# top_power.net
KiCad netlist of a schematic drawn in Altium Designer
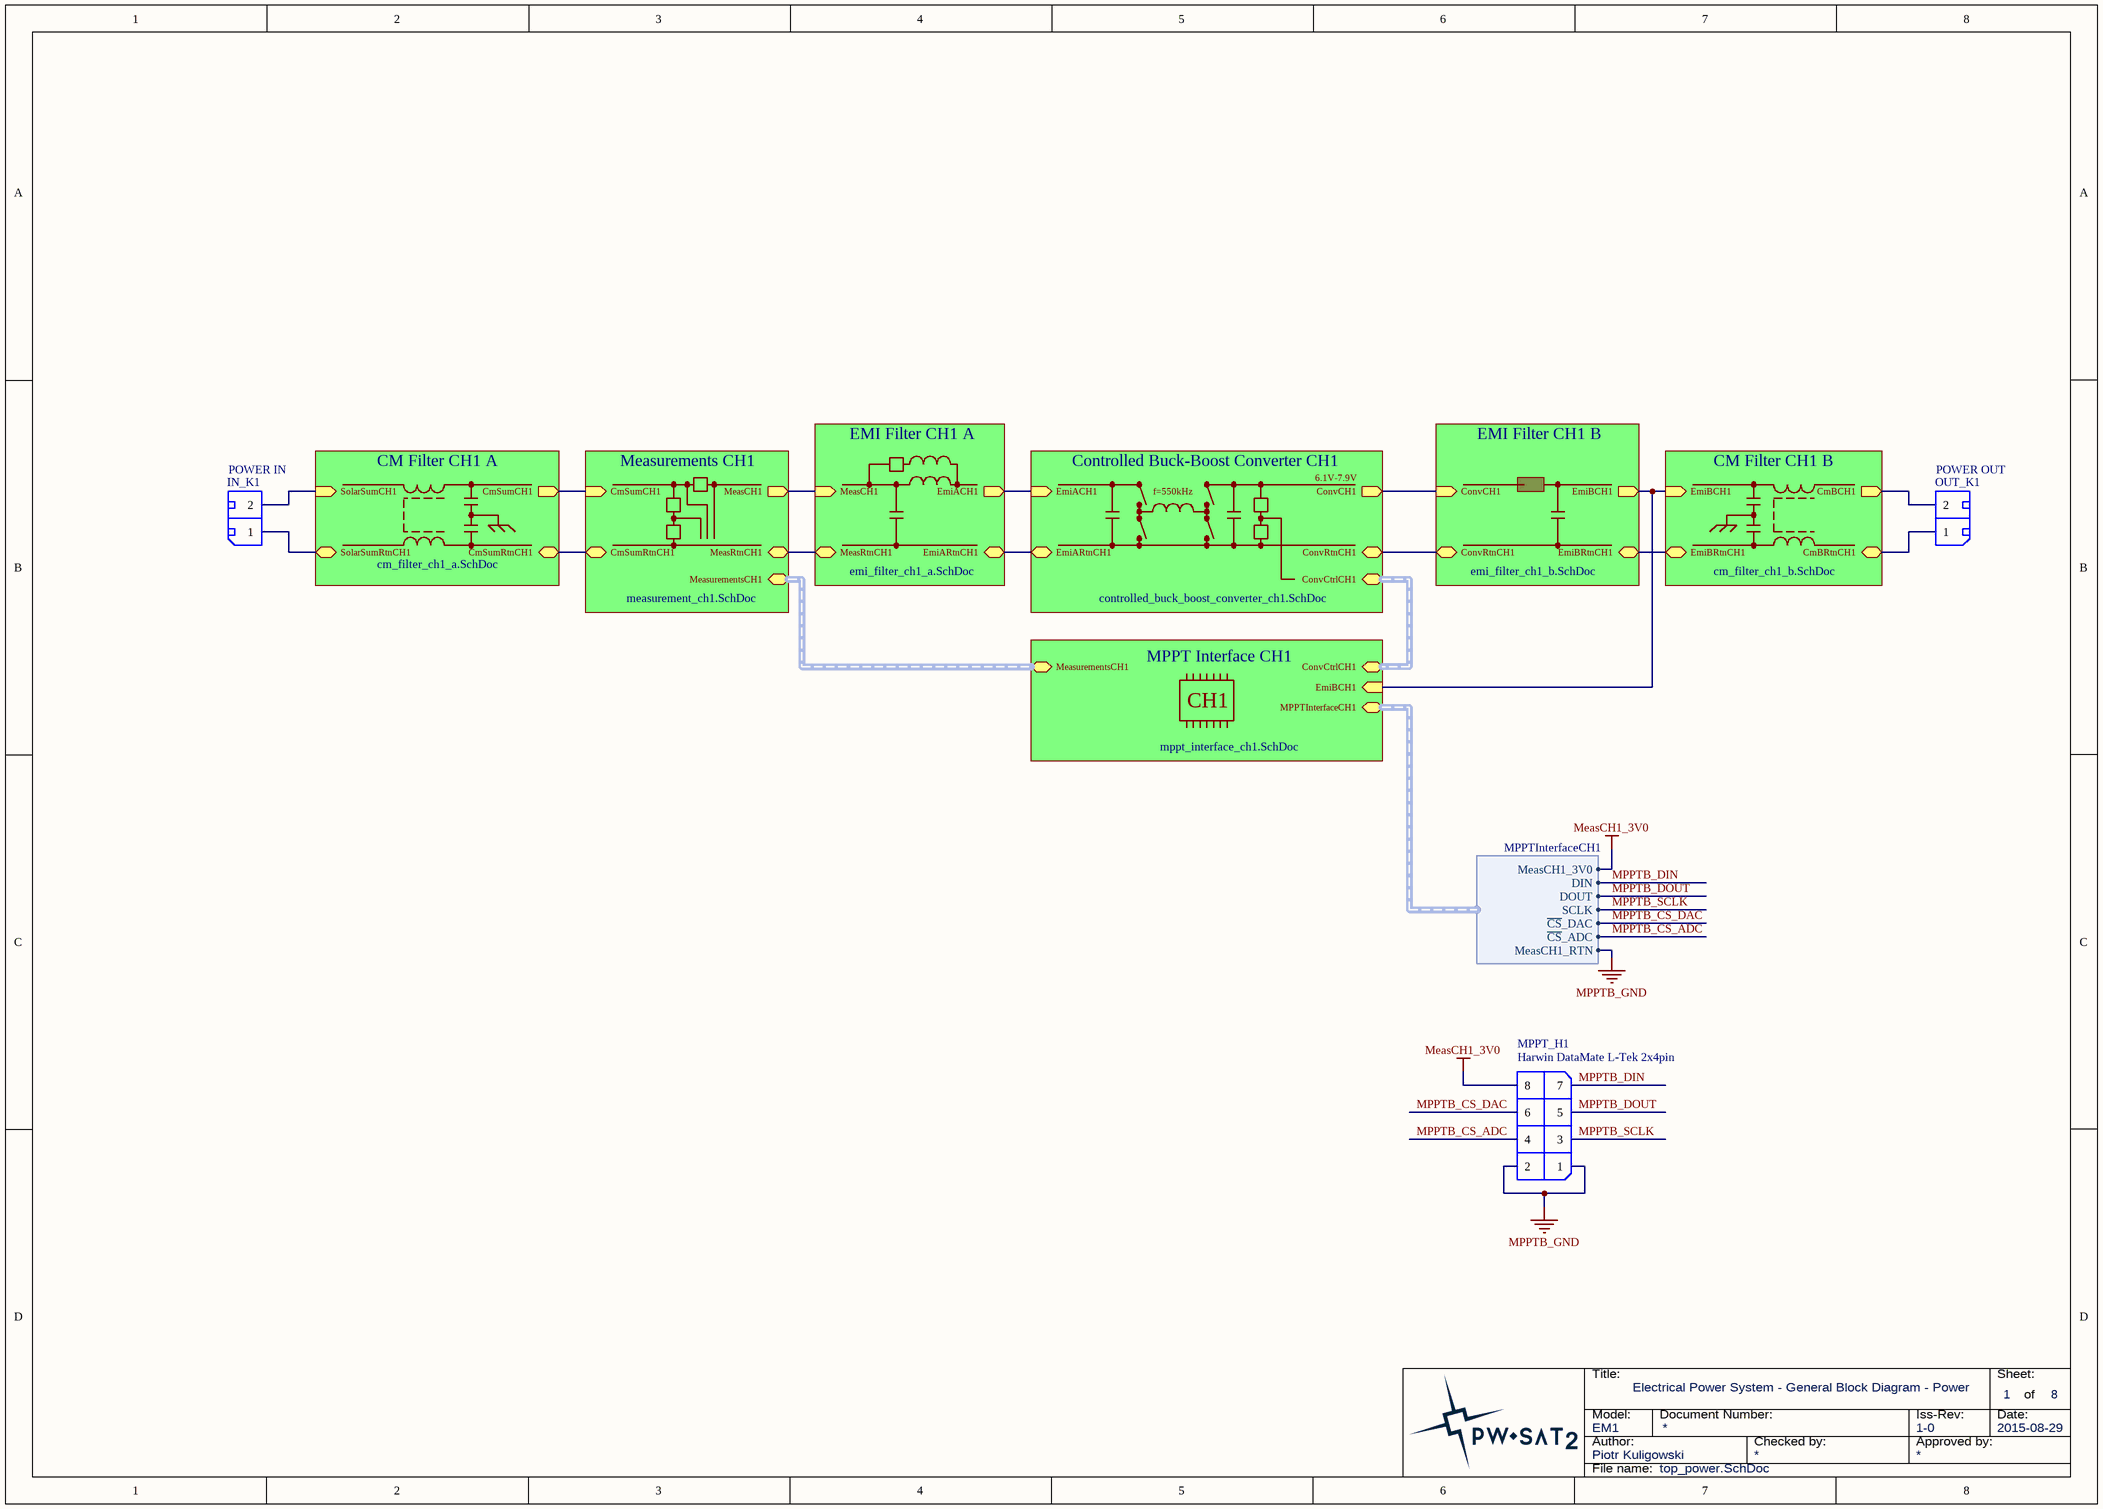
[diagram p0: top_power.SchDoc]

(export (version "E")
  (design (tool "Eeschema 10.0.6"))
  (components
    (comp (ref "IN_K1")
      (value "TB-2.5-PD-xx")
      (footprint "TerminalBlock_Spring_2.54_2-R")
      (description "Terminal block with spring, 2-pin, 2.54mm pitch, right angle.")
      (fields (field (name "PROVIDERPARTNUMBER") "POWER IN") (field (name "PROVIDER") "TME.eu"))
      (libsource (lib "connectors_printed-circuit-board") (part "TerminalBlock_Spring_2.54_2-R"))
    )
    (comp (ref "MPPT_H1")
      (value "Harwin DataMate L-Tek 2x4pin")
      (footprint "Harwin_Datamate_L-Tek_M80-8670805")
      (description "Harwin DataMate L-Tek, 2mm pitch, 2x4pin.")
      (libsource (lib "connectors_printed-circuit-board") (part "Harwin_Datamate_L-Tek_2x4pin"))
    )
    (comp (ref "OUT_K1")
      (value "TB-2.5-PD-xx")
      (footprint "TerminalBlock_Spring_2.54_2-R")
      (description "Terminal block with spring, 2-pin, 2.54mm pitch, right angle.")
      (fields (field (name "PROVIDERPARTNUMBER") "POWER OUT") (field (name "PROVIDER") "TME.eu"))
      (libsource (lib "connectors_printed-circuit-board") (part "TerminalBlock_Spring_2.54_2-R"))
    )
  )
  (nets
    (net (code "2") (name "/CmBCH1") (class "Default")
      (node (ref "OUT_K1") (pin "2") (pinfunction "2_2") (pintype "passive"))
    )
    (net (code "3") (name "/CmBRtnCH1") (class "Default")
      (node (ref "OUT_K1") (pin "1") (pinfunction "1_1") (pintype "passive"))
    )
    (net (code "13") (name "/MPPTB_CS_ADC") (class "Default")
      (node (ref "MPPT_H1") (pin "4") (pinfunction "4_4") (pintype "passive"))
    )
    (net (code "14") (name "/MPPTB_CS_DAC") (class "Default")
      (node (ref "MPPT_H1") (pin "6") (pinfunction "6_6") (pintype "passive"))
    )
    (net (code "15") (name "/MPPTB_DIN") (class "Default")
      (node (ref "MPPT_H1") (pin "7") (pinfunction "7_7") (pintype "passive"))
    )
    (net (code "16") (name "/MPPTB_DOUT") (class "Default")
      (node (ref "MPPT_H1") (pin "5") (pinfunction "5_5") (pintype "passive"))
    )
    (net (code "17") (name "/MPPTB_SCLK") (class "Default")
      (node (ref "MPPT_H1") (pin "3") (pinfunction "3_3") (pintype "passive"))
    )
    (net (code "21") (name "/SolarSumCH1") (class "Default")
      (node (ref "IN_K1") (pin "2") (pinfunction "2_2") (pintype "passive"))
    )
    (net (code "22") (name "/SolarSumRtnCH1") (class "Default")
      (node (ref "IN_K1") (pin "1") (pinfunction "1_1") (pintype "passive"))
    )
    (net (code "24") (name "MPPTB_GND") (class "Default")
      (node (ref "MPPT_H1") (pin "1") (pinfunction "1_1") (pintype "passive"))
      (node (ref "MPPT_H1") (pin "2") (pinfunction "2_2") (pintype "passive"))
    )
    (net (code "25") (name "MeasCH1_3V0") (class "Default")
      (node (ref "MPPT_H1") (pin "8") (pinfunction "8_8") (pintype "passive"))
    )
  )
)
